# CW340_PSU_VCCAUX.net
KiCad netlist of a schematic drawn in Altium Designer
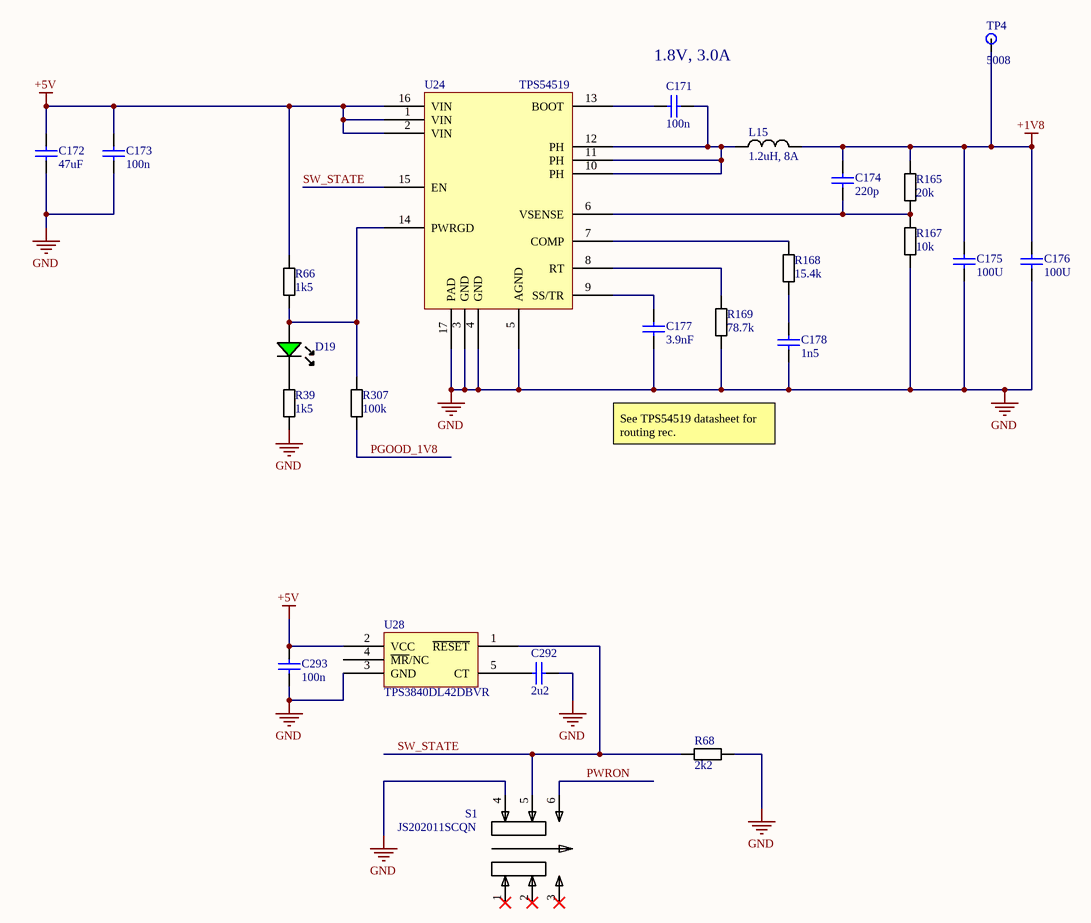
[diagram p0: CW340_PSU_VCCAUX.SchDoc]

(export (version "E")
  (design (tool "Eeschema 10.0.6"))
  (components
    (comp (ref "C171")
      (value "100n")
      (footprint "CAPC0603_M")
      (description "100n, 0603")
      (fields (field (name "PART NUMBER") "CCHIP-100n-0603"))
      (libsource (lib "NewAE_AltiumLib") (part "CAP"))
    )
    (comp (ref "C172")
      (value "47uF")
      (footprint "CAPC3225X20N")
      (description "47u, 10V, 1210, Ceramic")
      (fields (field (name "PART NUMBER") "CCHIP-47u-1210") (field (name "TOLERANCE") "20%"))
      (libsource (lib "NewAE_AltiumLib") (part "CAP"))
    )
    (comp (ref "C173")
      (value "100n")
      (footprint "CAPC0603_M")
      (description "100n, 0603")
      (fields (field (name "PART NUMBER") "CCHIP-100n-0603"))
      (libsource (lib "NewAE_AltiumLib") (part "CAP"))
    )
    (comp (ref "C174")
      (value "220p")
      (footprint "RESC1608X55N")
      (description "CAP CER 220PF 250V X7R 0603")
      (fields (field (name "PART NUMBER") "CCHIP-220P-0603-250V") (field (name "TOLERANCE") "±10%"))
      (libsource (lib "NewAE_AltiumLib") (part "CAP"))
    )
    (comp (ref "C175")
      (value "100U")
      (footprint "CAPC1206_M")
      (description "CAP CER 100UF 6.3V X5R 1206")
      (fields (field (name "PART NUMBER") "CCHIP-100u-1206-6.3v"))
      (libsource (lib "NewAE_AltiumLib") (part "CAP"))
    )
    (comp (ref "C176")
      (value "100U")
      (footprint "CAPC1206_M")
      (description "CAP CER 100UF 6.3V X5R 1206")
      (fields (field (name "PART NUMBER") "CCHIP-100u-1206-6.3v"))
      (libsource (lib "NewAE_AltiumLib") (part "CAP"))
    )
    (comp (ref "C177")
      (value "3.9nF")
      (footprint "CAPC0603_M")
      (description "3n9, 0603")
      (fields (field (name "PART NUMBER") "CCHIP-3n9-0603") (field (name "TOLERANCE") "1%"))
      (libsource (lib "NewAE_AltiumLib") (part "CAP"))
    )
    (comp (ref "C178")
      (value "1n5")
      (footprint "RESC1608X55N")
      (description "CAP CER 1500PF 100V X7R 0603")
      (fields (field (name "PART NUMBER") "CCHIP-1N5-0603-100V") (field (name "TOLERANCE") "±10%"))
      (libsource (lib "NewAE_AltiumLib") (part "CAP"))
    )
    (comp (ref "C292")
      (value "2u2")
      (footprint "CAPC0603_M")
      (description "2u2, 0603")
      (fields (field (name "PART NUMBER") "CCHIP-2u2-0603"))
      (libsource (lib "NewAE_AltiumLib") (part "CAP"))
    )
    (comp (ref "C293")
      (value "100n")
      (footprint "CAPC0603_M")
      (description "100n, 0603")
      (fields (field (name "PART NUMBER") "CCHIP-100n-0603"))
      (libsource (lib "NewAE_AltiumLib") (part "CAP"))
    )
    (comp (ref "D19")
      (value "LED, 0603, Green")
      (footprint "LED-0603-GREEN")
      (description "Chip LED, Green")
      (fields (field (name "PART NUMBER") "LEDCHIP_0603_GREEN"))
      (libsource (lib "NewAE_AltiumLib") (part "LED_GREEN"))
    )
    (comp (ref "L15")
      (value "1.2uH, 8A")
      (footprint "XAL5030-122")
      (description "1.2uH, 8A RMS, 12A SAT")
      (fields (field (name "PART NUMBER") "XAL5030-122"))
      (libsource (lib "NewAE_AltiumLib") (part "IND"))
    )
    (comp (ref "R39")
      (value "1k5")
      (footprint "RESC1608X55N")
      (description "1k5 res, 0603, 1%, 1/10W")
      (fields (field (name "PART NUMBER") "RCHIP-1K5-0603") (field (name "TOLERANCE") "1%"))
      (libsource (lib "NewAE_AltiumLib") (part "RES-EU"))
    )
    (comp (ref "R66")
      (value "1k5")
      (footprint "RESC1608X55N")
      (description "1k5 res, 0603, 1%, 1/10W")
      (fields (field (name "PART NUMBER") "RCHIP-1K5-0603") (field (name "TOLERANCE") "1%"))
      (libsource (lib "") (part "RES-EU_1"))
    )
    (comp (ref "R68")
      (value "2k2")
      (footprint "RESC1608X55N")
      (description "2k2 res, 0603, 1%, 1/10W")
      (fields (field (name "PART NUMBER") "RCHIP-2K2-0603") (field (name "TOLERANCE") "1%"))
      (libsource (lib "") (part "RES-EU_2"))
    )
    (comp (ref "R165")
      (value "20k")
      (footprint "RESC1608X55N")
      (description "20k res, 0603, 1%, 1/10W")
      (fields (field (name "PART NUMBER") "RCHIP-20K-0603") (field (name "TOLERANCE") "1%"))
      (libsource (lib "NewAE_AltiumLib") (part "RES-EU"))
    )
    (comp (ref "R167")
      (value "10k")
      (footprint "RESC1608X55N")
      (description "10k res, 0603, 1%, 1/10W")
      (fields (field (name "PART NUMBER") "RCHIP-10K-0603") (field (name "TOLERANCE") "1%"))
      (libsource (lib "NewAE_AltiumLib") (part "RES-EU"))
    )
    (comp (ref "R168")
      (value "15.4k")
      (footprint "RESC1608X55N")
      (description "15k4 res, 0603, 1%, 1/10W")
      (fields (field (name "PART NUMBER") "RCHIP-15k4-0603") (field (name "TOLERANCE") "1%"))
      (libsource (lib "NewAE_AltiumLib") (part "RES-EU"))
    )
    (comp (ref "R169")
      (value "78.7k")
      (footprint "RESC1608X55N")
      (description "78k7 res, 0603, 1%, 1/10W")
      (fields (field (name "PART NUMBER") "RCHIP-78k7-0603") (field (name "TOLERANCE") "1%"))
      (libsource (lib "NewAE_AltiumLib") (part "RES-EU"))
    )
    (comp (ref "R307")
      (value "100k")
      (footprint "RESC1608X55N")
      (description "100k res, 0603, 1%, 1/10W")
      (fields (field (name "PART NUMBER") "RCHIP-100K-0603") (field (name "TOLERANCE") "1%"))
      (libsource (lib "NewAE_AltiumLib") (part "RES-EU"))
    )
    (comp (ref "S1")
      (value "JS202011SCQN")
      (footprint "SW_JS202011SCQN")
      (description "DPDT SMD Switch, 300mA")
      (libsource (lib "NewAE_AltiumLib") (part "JS202011SCQN"))
    )
    (comp (ref "TP4")
      (value "5008")
      (footprint "KEYSTONE5008")
      (description "TEST POINT PC COMPACT .063\"D ORG")
      (fields (field (name "PART NUMBER") "KEYSTONE_5008"))
      (libsource (lib "NewAE_AltiumLib") (part "KEYSTONE_5008"))
    )
    (comp (ref "U24")
      (value "TPS54519")
      (footprint "QFN50P300X300X80_HS-17N")
      (description "6V Input, 5A, SMPS")
      (libsource (lib "NewAE_AltiumLib") (part "TPS54519"))
    )
    (comp (ref "U28")
      (value "TPS3840DL42DBVR")
      (footprint "SOT23-5P95_285X145L45X40")
      (description "Reset Supervisor")
      (libsource (lib "NewAE_AltiumLib") (part "TPS3840DL"))
    )
  )
  (nets
    (net (code "1") (name "+1V8") (class "Default")
      (node (ref "C174") (pin "1") (pinfunction "1_1") (pintype "passive"))
      (node (ref "C175") (pin "1") (pinfunction "1_1") (pintype "passive"))
      (node (ref "C176") (pin "1") (pinfunction "1_1") (pintype "passive"))
      (node (ref "L15") (pin "2") (pinfunction "2_2") (pintype "passive"))
      (node (ref "R165") (pin "1") (pinfunction "1_1") (pintype "passive"))
      (node (ref "TP4") (pin "1") (pinfunction "1_1") (pintype "passive"))
    )
    (net (code "2") (name "+5V") (class "Default")
      (node (ref "C172") (pin "1") (pinfunction "1_1") (pintype "passive"))
      (node (ref "C173") (pin "2") (pinfunction "2_2") (pintype "passive"))
      (node (ref "C293") (pin "2") (pinfunction "2_2") (pintype "passive"))
      (node (ref "R66") (pin "2") (pinfunction "2_2") (pintype "passive"))
      (node (ref "U24") (pin "1") (pinfunction "VIN_1") (pintype "passive"))
      (node (ref "U24") (pin "16") (pinfunction "VIN_16") (pintype "passive"))
      (node (ref "U24") (pin "2") (pinfunction "VIN_2") (pintype "passive"))
      (node (ref "U28") (pin "2") (pinfunction "VCC_2") (pintype "passive"))
    )
    (net (code "3") (name "/PGOOD_1V8") (class "Default")
      (node (ref "R307") (pin "2") (pinfunction "2_2") (pintype "passive"))
    )
    (net (code "4") (name "/PWRON") (class "Default")
      (node (ref "S1") (pin "6") (pinfunction "6_6") (pintype "passive"))
    )
    (net (code "5") (name "/SW_STATE") (class "Default")
      (node (ref "R68") (pin "1") (pinfunction "1_1") (pintype "passive"))
      (node (ref "S1") (pin "5") (pinfunction "5_5") (pintype "passive"))
      (node (ref "U24") (pin "15") (pinfunction "EN_15") (pintype "passive"))
      (node (ref "U28") (pin "1") (pinfunction "~{RESET}_1") (pintype "open_collector"))
    )
    (net (code "6") (name "GND") (class "Default")
      (node (ref "C172") (pin "2") (pinfunction "2_2") (pintype "passive"))
      (node (ref "C173") (pin "1") (pinfunction "1_1") (pintype "passive"))
      (node (ref "C175") (pin "2") (pinfunction "2_2") (pintype "passive"))
      (node (ref "C176") (pin "2") (pinfunction "2_2") (pintype "passive"))
      (node (ref "C177") (pin "2") (pinfunction "2_2") (pintype "passive"))
      (node (ref "C178") (pin "2") (pinfunction "2_2") (pintype "passive"))
      (node (ref "C292") (pin "2") (pinfunction "2_2") (pintype "passive"))
      (node (ref "C293") (pin "1") (pinfunction "1_1") (pintype "passive"))
      (node (ref "R167") (pin "2") (pinfunction "2_2") (pintype "passive"))
      (node (ref "R169") (pin "2") (pinfunction "2_2") (pintype "passive"))
      (node (ref "R39") (pin "2") (pinfunction "2_2") (pintype "passive"))
      (node (ref "R68") (pin "2") (pinfunction "2_2") (pintype "passive"))
      (node (ref "S1") (pin "4") (pinfunction "4_4") (pintype "passive"))
      (node (ref "U24") (pin "17") (pinfunction "PAD_17") (pintype "passive"))
      (node (ref "U24") (pin "3") (pinfunction "GND_3") (pintype "passive"))
      (node (ref "U24") (pin "4") (pinfunction "GND_4") (pintype "passive"))
      (node (ref "U24") (pin "5") (pinfunction "AGND_5") (pintype "passive"))
      (node (ref "U28") (pin "3") (pinfunction "GND_3") (pintype "passive"))
    )
    (net (code "7") (name "Net-(C171-Pad2)") (class "Default")
      (node (ref "C171") (pin "2") (pinfunction "2_2") (pintype "passive"))
      (node (ref "L15") (pin "1") (pinfunction "1_1") (pintype "passive"))
      (node (ref "U24") (pin "10") (pinfunction "PH_10") (pintype "passive"))
      (node (ref "U24") (pin "11") (pinfunction "PH_11") (pintype "passive"))
      (node (ref "U24") (pin "12") (pinfunction "PH_12") (pintype "passive"))
    )
    (net (code "8") (name "Net-(C178-Pad1)") (class "Default")
      (node (ref "C178") (pin "1") (pinfunction "1_1") (pintype "passive"))
      (node (ref "R168") (pin "2") (pinfunction "2_2") (pintype "passive"))
    )
    (net (code "9") (name "Net-(D19-PadK)") (class "Default")
      (node (ref "D19") (pin "K") (pinfunction "K_K") (pintype "passive"))
      (node (ref "R39") (pin "1") (pinfunction "1_1") (pintype "passive"))
    )
    (net (code "10") (name "Net-(U24-BOOT)") (class "Default")
      (node (ref "C171") (pin "1") (pinfunction "1_1") (pintype "passive"))
      (node (ref "U24") (pin "13") (pinfunction "BOOT_13") (pintype "passive"))
    )
    (net (code "11") (name "Net-(U24-COMP)") (class "Default")
      (node (ref "R168") (pin "1") (pinfunction "1_1") (pintype "passive"))
      (node (ref "U24") (pin "7") (pinfunction "COMP_7") (pintype "passive"))
    )
    (net (code "12") (name "Net-(U24-PWRGD)") (class "Default")
      (node (ref "D19") (pin "A") (pinfunction "A_A") (pintype "passive"))
      (node (ref "R307") (pin "1") (pinfunction "1_1") (pintype "passive"))
      (node (ref "R66") (pin "1") (pinfunction "1_1") (pintype "passive"))
      (node (ref "U24") (pin "14") (pinfunction "PWRGD_14") (pintype "passive"))
    )
    (net (code "13") (name "Net-(U24-RT)") (class "Default")
      (node (ref "R169") (pin "1") (pinfunction "1_1") (pintype "passive"))
      (node (ref "U24") (pin "8") (pinfunction "RT_8") (pintype "passive"))
    )
    (net (code "14") (name "Net-(U24-SS{slash}TR)") (class "Default")
      (node (ref "C177") (pin "1") (pinfunction "1_1") (pintype "passive"))
      (node (ref "U24") (pin "9") (pinfunction "SS/TR_9") (pintype "passive"))
    )
    (net (code "15") (name "Net-(U24-VSENSE)") (class "Default")
      (node (ref "C174") (pin "2") (pinfunction "2_2") (pintype "passive"))
      (node (ref "R165") (pin "2") (pinfunction "2_2") (pintype "passive"))
      (node (ref "R167") (pin "1") (pinfunction "1_1") (pintype "passive"))
      (node (ref "U24") (pin "6") (pinfunction "VSENSE_6") (pintype "passive"))
    )
    (net (code "16") (name "Net-(U28-CT)") (class "Default")
      (node (ref "C292") (pin "1") (pinfunction "1_1") (pintype "passive"))
      (node (ref "U28") (pin "5") (pinfunction "CT_5") (pintype "passive"))
    )
    (net (code "17") (name "unconnected-(S1-Pad1)") (class "Default")
      (node (ref "S1") (pin "1") (pinfunction "1_1") (pintype "passive+no_connect"))
    )
    (net (code "18") (name "unconnected-(S1-Pad2)") (class "Default")
      (node (ref "S1") (pin "2") (pinfunction "2_2") (pintype "passive+no_connect"))
    )
    (net (code "19") (name "unconnected-(S1-Pad3)") (class "Default")
      (node (ref "S1") (pin "3") (pinfunction "3_3") (pintype "passive+no_connect"))
    )
    (net (code "20") (name "unconnected-(U28-~{MR}{slash}NC-Pad4)") (class "Default")
      (node (ref "U28") (pin "4") (pinfunction "~{MR}/NC_4") (pintype "passive"))
    )
  )
)
